# Eload_Power_Module_-_Gen_2_Rev_3.net
KiCad netlist of a schematic drawn in Altium Designer
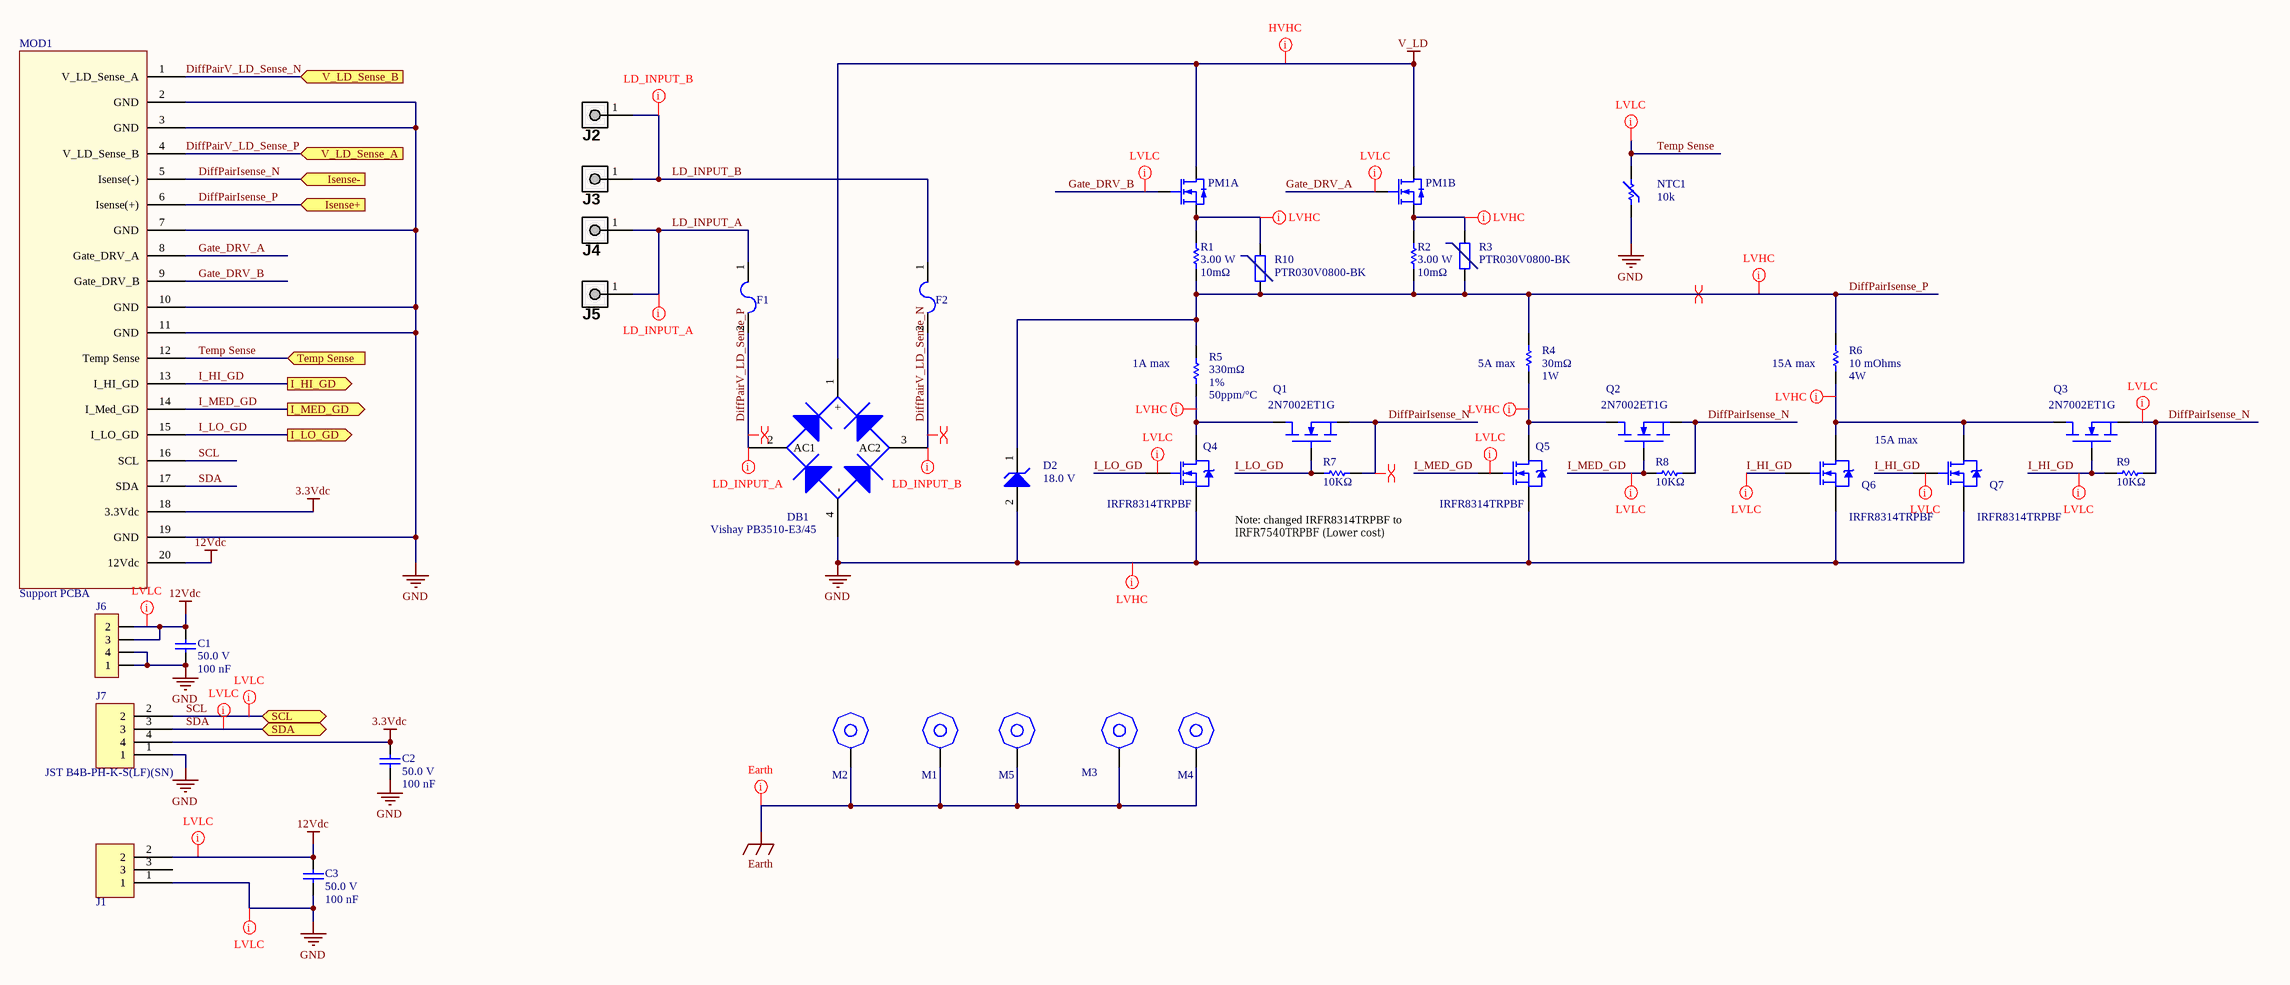
[diagram p0: Eload Power Module - Gen 2 Rev 3.SchDoc]

(export (version "E")
  (design (tool "Eeschema 10.0.6"))
  (components
    (comp (ref "C1")
      (value "Cap")
      (footprint "Cap,0805")
      (description "Capacitor; Ceramic; Cap 0.1 uF; Tol 5%; Vol-Rtg 50 VDC; SMT; 0805; X7R; Tape & Reel")
      (fields
        (field (name "MANUFACTURER PART NUMBER") "08055C104JAT2A")
        (field (name "VOLTAGE RATING (DC)") "50.0 V")
        (field (name "CAPACITANCE") "100 nF")
      )
      (libsource (lib "Master SEPT_2019") (part "Cap,0805,100nf,50V,5%,08055C104JAT2A"))
    )
    (comp (ref "C2")
      (value "Cap")
      (footprint "Cap,0805")
      (description "Capacitor; Ceramic; Cap 0.1 uF; Tol 5%; Vol-Rtg 50 VDC; SMT; 0805; X7R; Tape & Reel")
      (fields
        (field (name "MANUFACTURER PART NUMBER") "08055C104JAT2A")
        (field (name "VOLTAGE RATING (DC)") "50.0 V")
        (field (name "CAPACITANCE") "100 nF")
      )
      (libsource (lib "Master SEPT_2019") (part "Cap,0805,100nf,50V,5%,08055C104JAT2A"))
    )
    (comp (ref "C3")
      (value "Cap")
      (footprint "Cap,0805")
      (description "Capacitor; Ceramic; Cap 0.1 uF; Tol 5%; Vol-Rtg 50 VDC; SMT; 0805; X7R; Tape & Reel")
      (fields
        (field (name "MANUFACTURER PART NUMBER") "08055C104JAT2A")
        (field (name "VOLTAGE RATING (DC)") "50.0 V")
        (field (name "CAPACITANCE") "100 nF")
      )
      (libsource (lib "Master SEPT_2019") (part "Cap,0805,100nf,50V,5%,08055C104JAT2A"))
    )
    (comp (ref "D2")
      (value "MMSZ4705T1G")
      (footprint "SOD123")
      (description "Zener Diode 18V 500mW ±5% Surface Mount SOD-123")
      (fields (field (name "MANUFACTURER") "ON Semiconductor") (field (name "VOLTAGE RATING (DC)") "18.0 V"))
      (libsource (lib "Master Oct28_2018") (part "diode,Zener, 18V,500mW, SOD123,MMSZ4705T1G"))
    )
    (comp (ref "DB1")
      (value "Vishay PB3510-E3/45")
      (footprint "4-ESIP with Heat Sink")
      (description "RECTIFIER BRIDGE 1000V 35A PB")
      (fields (field (name "MANUFACTURER PART NUMBER") "PB3510-E3/45") (field (name "VOLTAGE") "1000"))
      (libsource (lib "Master JULY2019") (part "diode, bridge, 35A, 1000V,  PB3510-E3/45"))
    )
    (comp (ref "F1")
      (value "FUSE CERAMIC 30A 500VAC/VDC 3AB")
      (footprint "Fuse,TH,Vertical,0505030.MXEP")
      (fields (field (name "MANUFACTURER") "Littelfuse Inc."))
      (libsource (lib "Master Oct28_2018") (part "Fuse,30A,500VAC/VDC,Leaded"))
    )
    (comp (ref "F2")
      (value "FUSE CERAMIC 30A 500VAC/VDC 3AB")
      (footprint "Fuse,TH,Vertical,0505030.MXEP")
      (fields (field (name "MANUFACTURER") "Littelfuse Inc."))
      (libsource (lib "Master Oct28_2018") (part "Fuse,30A,500VAC/VDC,Leaded"))
    )
    (comp (ref "J1")
      (value "2-644861-3")
      (footprint "Connector,TE,3-Pin,Male,Vert,2-644861-3")
      (description "Connector Header Through Hole 3 position 0.100\" (2.54mm)")
      (libsource (lib "Master JULY2019") (part "Conntector, though hole, TE, 3pin, 2.54mm,2-644861-3"))
    )
    (comp (ref "J2")
      (value "wire teminal, lugs, screw, Keystone 8197")
      (footprint "Keystone 8197")
      (fields (field (name "MANUFACTURER PART NUMBER") "8197"))
      (libsource (lib "Master JULY2019") (part "wire teminal, lugs, screw, Keystone 8197"))
    )
    (comp (ref "J3")
      (value "wire teminal, lugs, screw, Keystone 8197")
      (footprint "Keystone 8197")
      (fields (field (name "MANUFACTURER PART NUMBER") "8197"))
      (libsource (lib "Master JULY2019") (part "wire teminal, lugs, screw, Keystone 8197"))
    )
    (comp (ref "J4")
      (value "wire teminal, lugs, screw, Keystone 8197")
      (footprint "Keystone 8197")
      (fields (field (name "MANUFACTURER PART NUMBER") "8197"))
      (libsource (lib "Master JULY2019") (part "wire teminal, lugs, screw, Keystone 8197"))
    )
    (comp (ref "J5")
      (value "wire teminal, lugs, screw, Keystone 8197")
      (footprint "Keystone 8197")
      (fields (field (name "MANUFACTURER PART NUMBER") "8197"))
      (libsource (lib "Master JULY2019") (part "wire teminal, lugs, screw, Keystone 8197"))
    )
    (comp (ref "J6")
      (value "0022112042")
      (footprint "conn, molex, 0.1\", 4 pin")
      (description "Connector Header Through Hole 4 position 0.100\" (2.54mm)")
      (fields (field (name "MANUFACTURER") "Molex"))
      (libsource (lib "Master JULY2019") (part "Connector,Through Hole,Molex,2.54mm,4Pin,Vert"))
    )
    (comp (ref "J7")
      (value "JST B4B-PH-K-S(LF)(SN)")
      (footprint "Conn, JST, 4 pin, 2mm spacing Right Angle")
      (description "PH Series 4 Position 2 mm Pitch Through Hole Crimp Top Entry Shrouded Header")
      (fields (field (name "MANUFACTURER PART NUMBER") "B4B-PH-K-S(LF)(SN)"))
      (libsource (lib "Master JULY2019") (part "Conntector, though hole, JST, 4pin, 2mm,B4B-PH-K-S(LF)(SN)"))
    )
    (comp (ref "M1")
      (value "M3 hex Standoff")
      (footprint "Standoff,Hex,M3,8mm")
      (description "HEX STANDOFF M3,generic")
      (libsource (lib "Master Oct28_2018") (part "Standoff, M3, Hex"))
    )
    (comp (ref "M2")
      (value "M3 hex Standoff")
      (footprint "Standoff,Hex,M3,8mm")
      (description "HEX STANDOFF M3,generic")
      (libsource (lib "Master Oct28_2018") (part "Standoff, M3, Hex"))
    )
    (comp (ref "M3")
      (value "M3 hex Standoff")
      (footprint "Standoff,Hex,M3,8mm")
      (description "HEX STANDOFF M3,generic")
      (libsource (lib "Master Oct28_2018") (part "Standoff, M3, Hex"))
    )
    (comp (ref "M4")
      (value "M3 hex Standoff")
      (footprint "Standoff,Hex,M3,8mm")
      (description "HEX STANDOFF M3,generic")
      (libsource (lib "Master Oct28_2018") (part "Standoff, M3, Hex"))
    )
    (comp (ref "M5")
      (value "M3 hex Standoff")
      (footprint "Standoff,Hex,M3,8mm")
      (description "HEX STANDOFF M3,generic")
      (libsource (lib "Master Oct28_2018") (part "Standoff, M3, Hex"))
    )
    (comp (ref "MOD1")
      (value "Support PCBA")
      (footprint "Mod,ELoad Gen 2 Rev 1 Support")
      (description "Eload Gen 2 Support PCBA")
      (libsource (lib "Master SEPT2019") (part "Mod,Eload Gen 2 rev 1 Support and Control"))
    )
    (comp (ref "NTC1")
      (value "NTCLE100E3103JT2")
      (footprint "NTC,TH,2.54mm Lead Spacing,NTCLE100E3103JT2")
      (description "THERMISTOR NTC 10KOHM 3977K BEAD")
      (fields
        (field (name "MANUFACTURER") "Vishay BC Components")
        (field (name "RESISTANCE IN OHMS @ 25°C") "10k")
      )
      (libsource (lib "Master JULY2019") (part "Sensor,Temp,NTC,10Kohm,0.75%, NTCLE100E3103JT2"))
    )
    (comp (ref "PM1")
      (value "Diode")
      (footprint "DUAL TO-247-RA WITH HEATSINK")
      (description "Dual RA Mosfet TO-247 with CPU cooler")
      (libsource (lib "Master JULY2019") (part "CC Load Power Module"))
    )
    (comp (ref "Q1")
      (value "2N7002ET1G")
      (footprint "SOT23-3")
      (description "Small Signal MOSFET, 60 V, 310 mA, Single, N-Channel, 3-Pin SOT-23, Pb-Free, Tape and Reel")
      (fields
        (field (name "MANUFACTURER") "ON Semiconductor")
        (field (name "MANUFACTURER PART NUMBER") "2N7002ET1G")
      )
      (libsource (lib "Master JULY2019") (part "MOSFET,N-Channel,SOT23,0.25A,60V,2N7002ET1G"))
    )
    (comp (ref "Q2")
      (value "2N7002ET1G")
      (footprint "SOT23-3")
      (description "Small Signal MOSFET, 60 V, 310 mA, Single, N-Channel, 3-Pin SOT-23, Pb-Free, Tape and Reel")
      (fields
        (field (name "MANUFACTURER") "ON Semiconductor")
        (field (name "MANUFACTURER PART NUMBER") "2N7002ET1G")
      )
      (libsource (lib "Master JULY2019") (part "MOSFET,N-Channel,SOT23,0.25A,60V,2N7002ET1G"))
    )
    (comp (ref "Q3")
      (value "2N7002ET1G")
      (footprint "SOT23-3")
      (description "Small Signal MOSFET, 60 V, 310 mA, Single, N-Channel, 3-Pin SOT-23, Pb-Free, Tape and Reel")
      (fields
        (field (name "MANUFACTURER") "ON Semiconductor")
        (field (name "MANUFACTURER PART NUMBER") "2N7002ET1G")
      )
      (libsource (lib "Master JULY2019") (part "MOSFET,N-Channel,SOT23,0.25A,60V,2N7002ET1G"))
    )
    (comp (ref "Q4")
      (value "Infineon IRFR8314TRPBF")
      (footprint "DPAK,3-Leads")
      (description "Single N-Channel 30 V 2.2 mOhm 36 nC HEXFET® Power Mosfet - DPAK")
      (fields (field (name "MANUFACTURER PART NUMBER") "IRFR8314TRPBF"))
      (libsource (lib "Master Oct28_2018") (part "Mosfet,Dpak, Nchannel,90A,30V, IRFR8314TRPBF"))
    )
    (comp (ref "Q5")
      (value "Infineon IRFR8314TRPBF")
      (footprint "DPAK,3-Leads")
      (description "Single N-Channel 30 V 2.2 mOhm 36 nC HEXFET® Power Mosfet - DPAK")
      (fields (field (name "MANUFACTURER PART NUMBER") "IRFR8314TRPBF"))
      (libsource (lib "Master Oct28_2018") (part "Mosfet,Dpak, Nchannel,90A,30V, IRFR8314TRPBF"))
    )
    (comp (ref "Q6")
      (value "Infineon IRFR8314TRPBF")
      (footprint "DPAK,3-Leads")
      (description "Single N-Channel 30 V 2.2 mOhm 36 nC HEXFET® Power Mosfet - DPAK")
      (fields (field (name "MANUFACTURER PART NUMBER") "IRFR8314TRPBF"))
      (libsource (lib "Master Oct28_2018") (part "Mosfet,Dpak, Nchannel,90A,30V, IRFR8314TRPBF"))
    )
    (comp (ref "Q7")
      (value "Infineon IRFR8314TRPBF")
      (footprint "DPAK,3-Leads")
      (description "Single N-Channel 30 V 2.2 mOhm 36 nC HEXFET® Power Mosfet - DPAK")
      (fields (field (name "MANUFACTURER PART NUMBER") "IRFR8314TRPBF"))
      (libsource (lib "Master Oct28_2018") (part "Mosfet,Dpak, Nchannel,90A,30V, IRFR8314TRPBF"))
    )
    (comp (ref "R1")
      (value "Res1")
      (footprint "Res 2512")
      (description "Resistor; Metal Film; Res 0.01 Ohms; Pwr-Rtg 3 W; Tol 1%; SMT; 2512; Current Sense")
      (fields
        (field (name "MANUFACTURER PART NUMBER") "CRA2512-FZ-R010ELF")
        (field (name "POWER RATING") "3.00 W")
        (field (name "RESISTANCE") "10mΩ")
      )
      (libsource (lib "Master Oct28_2018") (part "Res,2512,10mΩ,3.00W,±1%,CRA2512-FZ-R010ELF"))
    )
    (comp (ref "R2")
      (value "Res1")
      (footprint "Res 2512")
      (description "Resistor; Metal Film; Res 0.01 Ohms; Pwr-Rtg 3 W; Tol 1%; SMT; 2512; Current Sense")
      (fields
        (field (name "MANUFACTURER PART NUMBER") "CRA2512-FZ-R010ELF")
        (field (name "POWER RATING") "3.00 W")
        (field (name "RESISTANCE") "10mΩ")
      )
      (libsource (lib "Master Oct28_2018") (part "Res,2512,10mΩ,3.00W,±1%,CRA2512-FZ-R010ELF"))
    )
    (comp (ref "R3")
      (value "PTR030V0800-BK")
      (footprint "Fuse,PTC,10mmPitch,Radial, Disc")
      (description "PTC RESET FUSE 30V 8A RADIAL")
      (fields (field (name "MANUFACTURER") "Eaton - Electronics Division"))
      (libsource (lib "Master Mar2021") (part "Fuse,Resettable,8A,30V,ThoughHole,PTR030V0800-BK"))
    )
    (comp (ref "R4")
      (value "Ohmite LVM25FVR030E-TR")
      (footprint "Shunt,2512,SMD,Kalvin conn")
      (description "Resistors; Current Sense; SMD 1W 0.030 OHM 1%")
      (fields
        (field (name "MANUFACTURER PART NUMBER") "LVM25FVR030E-TR")
        (field (name "POWER RATING") "1W")
        (field (name "RESISTANCE") "30mΩ")
      )
      (libsource (lib "Master Oct28_2018") (part "Res, 2512, shunt, 30mΩ,1W, LVM25FVR030E-TR"))
    )
    (comp (ref "R5")
      (value "Res,1206,0.330Ohm,shunt,0.75W,1%,50ppm,KRL1632E-M-R330-F-T5")
      (footprint "Res,1206")
      (description "RES 0.33 OHM 1% 3/4W 1206")
      (fields
        (field (name "RESISTANCE") "330mΩ")
        (field (name "TOLERANCE") "1%")
        (field (name "TEMPERATURE COEFFICIENT") "50ppm/°C")
      )
      (libsource (lib "Master Oct28_2018") (part "Res,1206,0.330Ohm,shunt,0.75W,1%,50ppm,KRL1632E-M-R330-F-T5"))
    )
    (comp (ref "R6")
      (value "CSSH2728FT10L0")
      (footprint "Res,2827,4W")
      (fields
        (field (name "RESISTANCE") "10 mOhms")
        (field (name "TOLERANCE") "±1%")
        (field (name "POWER (WATTS)") "4W")
      )
      (libsource (lib "Master JULY2019") (part "Res,2827,shunt,10mΩ,1%,15ppm,CSSH2728FT10L0"))
    )
    (comp (ref "R7")
      (value "Vishay / Dale CRCW080510K0FKTA")
      (footprint "res, 0805, HD")
      (description "RES SMD 10K OHM 1% 1/8W 0805")
      (fields (field (name "RESISTANCE") "10KΩ"))
      (libsource (lib "Master Oct28_2018") (part "Res,0805,10.0kΩ,1%,100 ppm,CRCW080510K0FKTA"))
    )
    (comp (ref "R8")
      (value "Vishay / Dale CRCW080510K0FKTA")
      (footprint "res, 0805, HD")
      (description "RES SMD 10K OHM 1% 1/8W 0805")
      (fields (field (name "RESISTANCE") "10KΩ"))
      (libsource (lib "Master Oct28_2018") (part "Res,0805,10.0kΩ,1%,100 ppm,CRCW080510K0FKTA"))
    )
    (comp (ref "R9")
      (value "Vishay / Dale CRCW080510K0FKTA")
      (footprint "res, 0805, HD")
      (description "RES SMD 10K OHM 1% 1/8W 0805")
      (fields (field (name "RESISTANCE") "10KΩ"))
      (libsource (lib "Master Oct28_2018") (part "Res,0805,10.0kΩ,1%,100 ppm,CRCW080510K0FKTA"))
    )
    (comp (ref "R10")
      (value "PTR030V0800-BK")
      (footprint "Fuse,PTC,10mmPitch,Radial, Disc")
      (description "PTC RESET FUSE 30V 8A RADIAL")
      (fields (field (name "MANUFACTURER") "Eaton - Electronics Division"))
      (libsource (lib "Master Mar2021") (part "Fuse,Resettable,8A,30V,ThoughHole,PTR030V0800-BK"))
    )
  )
  (nets
    (net (code "1") (name "/DiffPairIsense_N") (class "Default")
      (node (ref "MOD1") (pin "5") (pinfunction "Isense(-)_5") (pintype "passive"))
      (node (ref "Q1") (pin "2") (pinfunction "S_2") (pintype "passive"))
      (node (ref "Q2") (pin "2") (pinfunction "S_2") (pintype "passive"))
      (node (ref "Q3") (pin "2") (pinfunction "S_2") (pintype "passive"))
      (node (ref "R7") (pin "2") (pinfunction "2_2") (pintype "passive"))
      (node (ref "R8") (pin "2") (pinfunction "2_2") (pintype "passive"))
      (node (ref "R9") (pin "1") (pinfunction "1_1") (pintype "passive"))
    )
    (net (code "2") (name "/DiffPairIsense_P") (class "Default")
      (node (ref "D2") (pin "1") (pinfunction "K_1") (pintype "passive"))
      (node (ref "MOD1") (pin "6") (pinfunction "Isense(+)_6") (pintype "passive"))
      (node (ref "R1") (pin "1") (pinfunction "1_1") (pintype "passive"))
      (node (ref "R10") (pin "1") (pinfunction "1_1") (pintype "passive"))
      (node (ref "R2") (pin "1") (pinfunction "1_1") (pintype "passive"))
      (node (ref "R3") (pin "1") (pinfunction "1_1") (pintype "passive"))
      (node (ref "R4") (pin "2") (pinfunction "2_2") (pintype "passive"))
      (node (ref "R5") (pin "1") (pinfunction "1_1") (pintype "passive"))
      (node (ref "R6") (pin "2") (pinfunction "2_2") (pintype "passive"))
    )
    (net (code "3") (name "/DiffPairV_LD_Sense_N") (class "Default")
      (node (ref "DB1") (pin "3") (pinfunction "AC2_3") (pintype "passive"))
      (node (ref "F2") (pin "2") (pinfunction "2_2") (pintype "passive"))
      (node (ref "MOD1") (pin "1") (pinfunction "V_LD_Sense_A_1") (pintype "passive"))
    )
    (net (code "4") (name "/DiffPairV_LD_Sense_P") (class "Default")
      (node (ref "DB1") (pin "2") (pinfunction "AC1_2") (pintype "passive"))
      (node (ref "F1") (pin "2") (pinfunction "2_2") (pintype "passive"))
      (node (ref "MOD1") (pin "4") (pinfunction "V_LD_Sense_B_4") (pintype "passive"))
    )
    (net (code "5") (name "/Gate_DRV_A") (class "Default")
      (node (ref "MOD1") (pin "8") (pinfunction "Gate_DRV_A_8") (pintype "passive"))
      (node (ref "PM1") (pin "4") (pinfunction "G_4") (pintype "passive"))
    )
    (net (code "6") (name "/Gate_DRV_B") (class "Default")
      (node (ref "MOD1") (pin "9") (pinfunction "Gate_DRV_B_9") (pintype "passive"))
      (node (ref "PM1") (pin "1") (pinfunction "G_1") (pintype "passive"))
    )
    (net (code "7") (name "/I_HI_GD") (class "Default")
      (node (ref "MOD1") (pin "13") (pinfunction "I_HI_GD_13") (pintype "passive"))
      (node (ref "Q3") (pin "1") (pinfunction "G_1") (pintype "passive"))
      (node (ref "Q6") (pin "1") (pinfunction "G_1") (pintype "passive"))
      (node (ref "Q7") (pin "1") (pinfunction "G_1") (pintype "passive"))
      (node (ref "R9") (pin "2") (pinfunction "2_2") (pintype "passive"))
    )
    (net (code "8") (name "/I_LO_GD") (class "Default")
      (node (ref "MOD1") (pin "15") (pinfunction "I_LO_GD_15") (pintype "passive"))
      (node (ref "Q1") (pin "1") (pinfunction "G_1") (pintype "passive"))
      (node (ref "Q4") (pin "1") (pinfunction "G_1") (pintype "passive"))
      (node (ref "R7") (pin "1") (pinfunction "1_1") (pintype "passive"))
    )
    (net (code "9") (name "/I_MED_GD") (class "Default")
      (node (ref "MOD1") (pin "14") (pinfunction "I_Med_GD_14") (pintype "passive"))
      (node (ref "Q2") (pin "1") (pinfunction "G_1") (pintype "passive"))
      (node (ref "Q5") (pin "1") (pinfunction "G_1") (pintype "passive"))
      (node (ref "R8") (pin "1") (pinfunction "1_1") (pintype "passive"))
    )
    (net (code "10") (name "/LD_INPUT_A") (class "Default")
      (node (ref "F1") (pin "1") (pinfunction "1_1") (pintype "passive"))
      (node (ref "J4") (pin "1") (pinfunction "1_1") (pintype "passive"))
      (node (ref "J5") (pin "1") (pinfunction "1_1") (pintype "passive"))
    )
    (net (code "11") (name "/LD_INPUT_B") (class "Default")
      (node (ref "F2") (pin "1") (pinfunction "1_1") (pintype "passive"))
      (node (ref "J2") (pin "1") (pinfunction "1_1") (pintype "passive"))
      (node (ref "J3") (pin "1") (pinfunction "1_1") (pintype "passive"))
    )
    (net (code "12") (name "/SCL") (class "Default")
      (node (ref "J7") (pin "2") (pinfunction "2_2") (pintype "passive"))
      (node (ref "MOD1") (pin "16") (pinfunction "SCL_16") (pintype "passive"))
    )
    (net (code "13") (name "/SDA") (class "Default")
      (node (ref "J7") (pin "3") (pinfunction "3_3") (pintype "passive"))
      (node (ref "MOD1") (pin "17") (pinfunction "SDA_17") (pintype "passive"))
    )
    (net (code "14") (name "/Temp Sense") (class "Default")
      (node (ref "MOD1") (pin "12") (pinfunction "Temp_Sense_12") (pintype "passive"))
      (node (ref "NTC1") (pin "2") (pinfunction "2_2") (pintype "passive"))
    )
    (net (code "15") (name "3.3Vdc") (class "Default")
      (node (ref "C2") (pin "2") (pinfunction "2_2") (pintype "passive"))
      (node (ref "J7") (pin "4") (pinfunction "4_4") (pintype "passive"))
      (node (ref "MOD1") (pin "18") (pinfunction "3.3Vdc_18") (pintype "passive"))
    )
    (net (code "16") (name "12Vdc") (class "Default")
      (node (ref "C1") (pin "2") (pinfunction "2_2") (pintype "passive"))
      (node (ref "C3") (pin "2") (pinfunction "2_2") (pintype "passive"))
      (node (ref "J1") (pin "2") (pinfunction "2_2") (pintype "passive"))
      (node (ref "J6") (pin "2") (pinfunction "2_2") (pintype "passive"))
      (node (ref "J6") (pin "3") (pinfunction "3_3") (pintype "passive"))
      (node (ref "MOD1") (pin "20") (pinfunction "12Vdc_20") (pintype "passive"))
    )
    (net (code "17") (name "Earth") (class "Default")
      (node (ref "M1") (pin "0") (pinfunction "0_0") (pintype "passive"))
      (node (ref "M2") (pin "0") (pinfunction "0_0") (pintype "passive"))
      (node (ref "M3") (pin "0") (pinfunction "0_0") (pintype "passive"))
      (node (ref "M4") (pin "0") (pinfunction "0_0") (pintype "passive"))
      (node (ref "M5") (pin "0") (pinfunction "0_0") (pintype "passive"))
    )
    (net (code "18") (name "GND") (class "Default")
      (node (ref "C1") (pin "1") (pinfunction "1_1") (pintype "passive"))
      (node (ref "C2") (pin "1") (pinfunction "1_1") (pintype "passive"))
      (node (ref "C3") (pin "1") (pinfunction "1_1") (pintype "passive"))
      (node (ref "D2") (pin "2") (pinfunction "A_2") (pintype "passive"))
      (node (ref "DB1") (pin "4") (pinfunction "-_4") (pintype "passive"))
      (node (ref "J1") (pin "1") (pinfunction "1_1") (pintype "passive"))
      (node (ref "J6") (pin "1") (pinfunction "1_1") (pintype "passive"))
      (node (ref "J6") (pin "4") (pinfunction "4_4") (pintype "passive"))
      (node (ref "J7") (pin "1") (pinfunction "1_1") (pintype "passive"))
      (node (ref "MOD1") (pin "10") (pinfunction "GND_10") (pintype "passive"))
      (node (ref "MOD1") (pin "11") (pinfunction "GND_11") (pintype "passive"))
      (node (ref "MOD1") (pin "19") (pinfunction "GND_19") (pintype "passive"))
      (node (ref "MOD1") (pin "2") (pinfunction "GND_2") (pintype "passive"))
      (node (ref "MOD1") (pin "3") (pinfunction "GND_3") (pintype "passive"))
      (node (ref "MOD1") (pin "7") (pinfunction "GND_7") (pintype "passive"))
      (node (ref "NTC1") (pin "1") (pinfunction "1_1") (pintype "passive"))
      (node (ref "Q4") (pin "2") (pinfunction "S_2") (pintype "passive"))
      (node (ref "Q5") (pin "2") (pinfunction "S_2") (pintype "passive"))
      (node (ref "Q6") (pin "2") (pinfunction "S_2") (pintype "passive"))
      (node (ref "Q7") (pin "2") (pinfunction "S_2") (pintype "passive"))
    )
    (net (code "19") (name "Net-(PM1A-S)") (class "Default")
      (node (ref "PM1") (pin "3") (pinfunction "S_3") (pintype "passive"))
      (node (ref "R1") (pin "2") (pinfunction "2_2") (pintype "passive"))
      (node (ref "R10") (pin "2") (pinfunction "2_2") (pintype "passive"))
    )
    (net (code "20") (name "Net-(PM1B-S)") (class "Default")
      (node (ref "PM1") (pin "6") (pinfunction "S_6") (pintype "passive"))
      (node (ref "R2") (pin "2") (pinfunction "2_2") (pintype "passive"))
      (node (ref "R3") (pin "2") (pinfunction "2_2") (pintype "passive"))
    )
    (net (code "21") (name "Net-(Q1-D)") (class "Default")
      (node (ref "Q1") (pin "3") (pinfunction "D_3") (pintype "passive"))
      (node (ref "Q4") (pin "3") (pinfunction "D_3") (pintype "passive"))
      (node (ref "R5") (pin "2") (pinfunction "2_2") (pintype "passive"))
    )
    (net (code "22") (name "Net-(Q2-D)") (class "Default")
      (node (ref "Q2") (pin "3") (pinfunction "D_3") (pintype "passive"))
      (node (ref "Q5") (pin "3") (pinfunction "D_3") (pintype "passive"))
      (node (ref "R4") (pin "1") (pinfunction "1_1") (pintype "passive"))
    )
    (net (code "23") (name "Net-(Q3-D)") (class "Default")
      (node (ref "Q3") (pin "3") (pinfunction "D_3") (pintype "passive"))
      (node (ref "Q6") (pin "3") (pinfunction "D_3") (pintype "passive"))
      (node (ref "Q7") (pin "3") (pinfunction "D_3") (pintype "passive"))
      (node (ref "R6") (pin "1") (pinfunction "1_1") (pintype "passive"))
    )
    (net (code "24") (name "V_LD") (class "Default")
      (node (ref "DB1") (pin "1") (pinfunction "+_1") (pintype "passive"))
      (node (ref "PM1") (pin "2") (pinfunction "D_2") (pintype "passive"))
      (node (ref "PM1") (pin "5") (pinfunction "D_5") (pintype "passive"))
    )
    (net (code "25") (name "unconnected-(J1-Pad3)") (class "Default")
      (node (ref "J1") (pin "3") (pinfunction "3_3") (pintype "passive"))
    )
  )
)
